# PennyMan_Ard_R3_Shield_v9.net
KiCad netlist of a schematic drawn in EAGLE
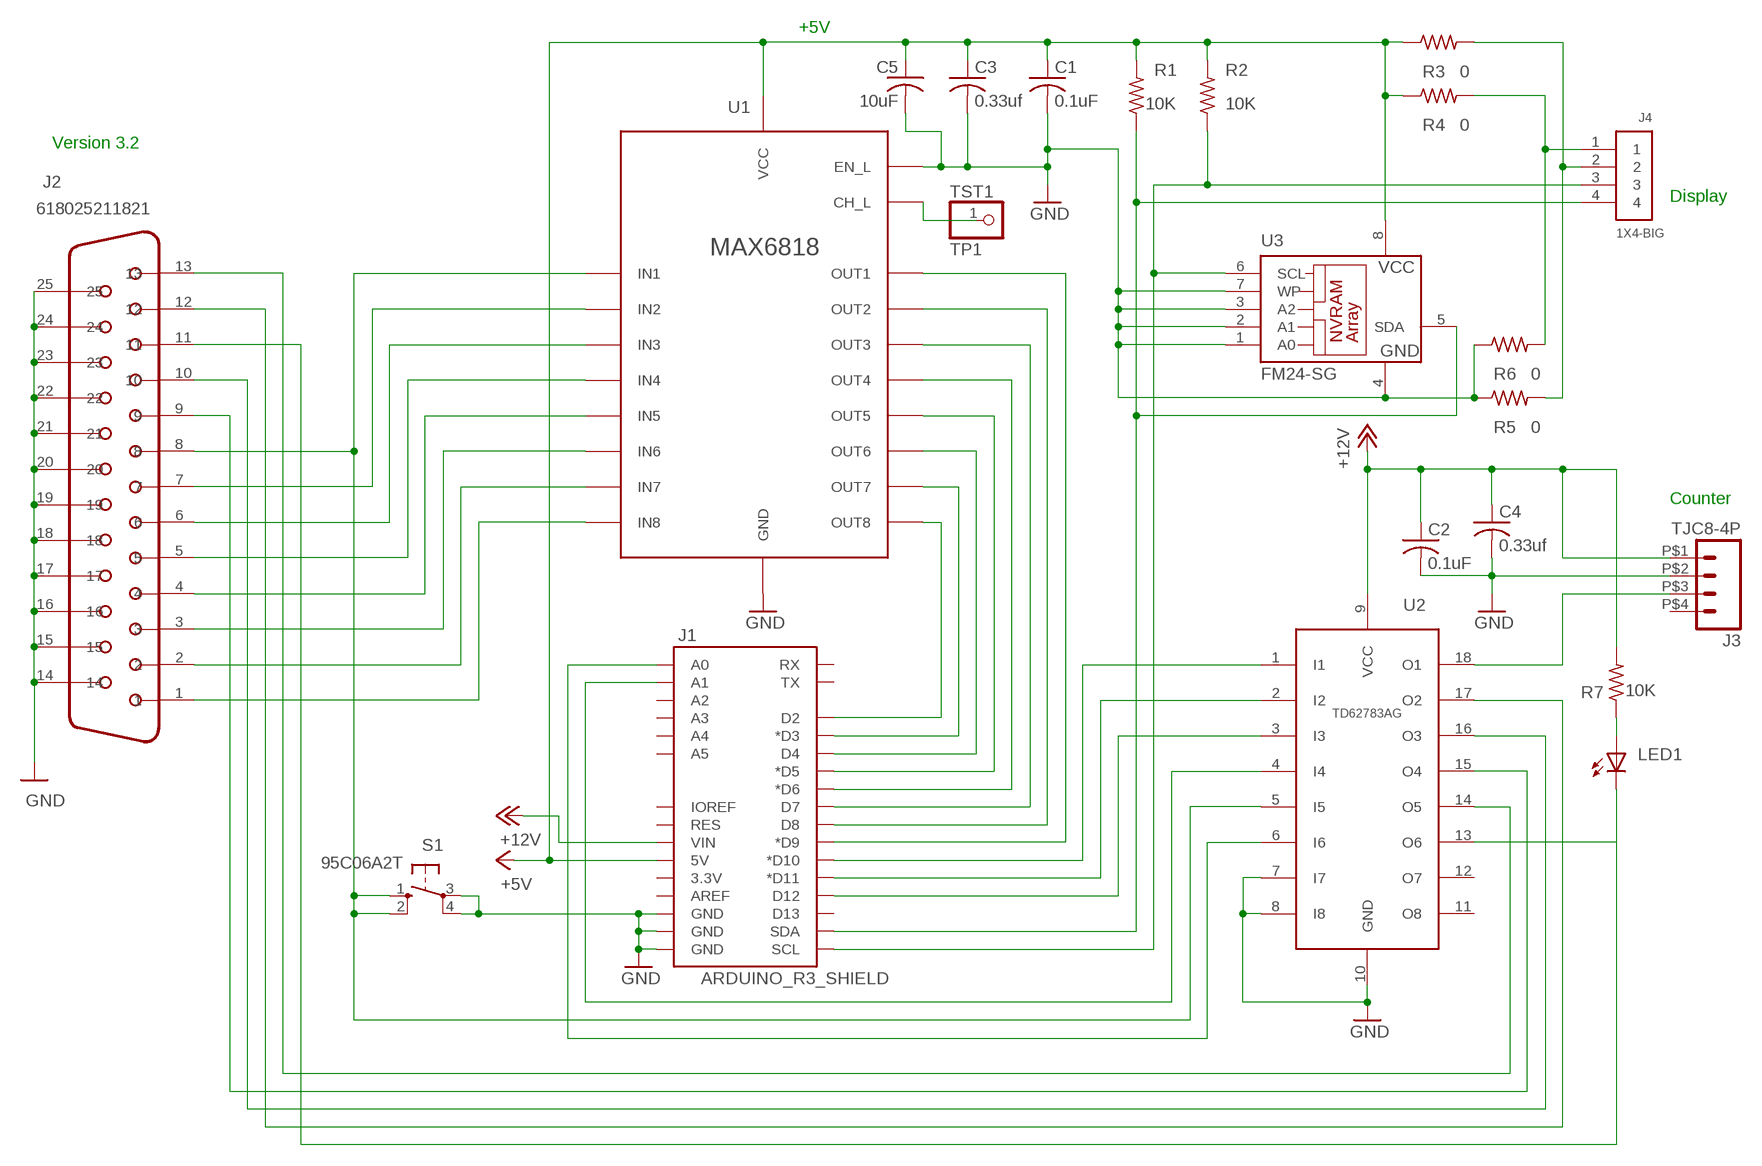
[diagram p0: schematic, sheet 1]

(export (version "E")
  (design (tool "Eeschema 10.0.6"))
  (components
    (comp (ref "C1")
      (value "0.1uF")
      (footprint "eagle-import:C0805")
      (libsource (lib "eagle-import") (part "C-USC0805"))
    )
    (comp (ref "C2")
      (value "0.1uF")
      (footprint "eagle-import:C0805")
      (libsource (lib "eagle-import") (part "C-USC0805"))
    )
    (comp (ref "C3")
      (value "0.33uf")
      (footprint "eagle-import:C1206")
      (libsource (lib "eagle-import") (part "C-USC1206"))
    )
    (comp (ref "C4")
      (value "0.33uf")
      (footprint "eagle-import:C1206")
      (libsource (lib "eagle-import") (part "C-USC1206"))
    )
    (comp (ref "C5")
      (value "10uF")
      (footprint "eagle-import:C1812")
      (libsource (lib "eagle-import") (part "C-USC1812"))
    )
    (comp (ref "J1")
      (value "ARDUINO_R3_SHIELD")
      (footprint "eagle-import:UNO_R3_SHIELD")
      (libsource (lib "eagle-import") (part "ARDUINO_R3_SHIELD"))
    )
    (comp (ref "J2")
      (value "618025211821")
      (footprint "eagle-import:618025211821")
      (libsource (lib "eagle-import") (part "618025211821"))
    )
    (comp (ref "J3")
      (value "TJC8-4P")
      (footprint "eagle-import:TJC8-4P")
      (libsource (lib "eagle-import") (part "TJC8-4P"))
    )
    (comp (ref "J4")
      (value "1X4-BIG")
      (footprint "eagle-import:1X04-BIG")
      (libsource (lib "eagle-import") (part "1X4-BIG"))
    )
    (comp (ref "LED1")
      (value "LEDSML0805")
      (footprint "eagle-import:SML0805")
      (libsource (lib "eagle-import") (part "LEDSML0805"))
    )
    (comp (ref "R1")
      (value "10K")
      (footprint "eagle-import:R0805")
      (libsource (lib "eagle-import") (part "R-US_R0805"))
    )
    (comp (ref "R2")
      (value "10K")
      (footprint "eagle-import:R0805")
      (libsource (lib "eagle-import") (part "R-US_R0805"))
    )
    (comp (ref "R3")
      (value "0")
      (footprint "eagle-import:R0805")
      (libsource (lib "eagle-import") (part "R-US_R0805"))
    )
    (comp (ref "R4")
      (value "0")
      (footprint "eagle-import:R0805")
      (libsource (lib "eagle-import") (part "R-US_R0805"))
    )
    (comp (ref "R5")
      (value "0")
      (footprint "eagle-import:R0805")
      (libsource (lib "eagle-import") (part "R-US_R0805"))
    )
    (comp (ref "R6")
      (value "0")
      (footprint "eagle-import:R0805")
      (libsource (lib "eagle-import") (part "R-US_R0805"))
    )
    (comp (ref "R7")
      (value "10K")
      (footprint "eagle-import:R0805")
      (libsource (lib "eagle-import") (part "R-US_R0805"))
    )
    (comp (ref "S1")
      (value "95C06A2T")
      (footprint "eagle-import:B3F-10XX")
      (libsource (lib "eagle-import") (part "10-XX"))
    )
    (comp (ref "TST1")
      (value "TP1")
      (footprint "eagle-import:1X01")
      (libsource (lib "eagle-import") (part "PINHD-1X1"))
    )
    (comp (ref "U1")
      (value "MAX6818")
      (footprint "eagle-import:SSOP20")
      (libsource (lib "eagle-import") (part "MAX6818"))
    )
    (comp (ref "U2")
      (value "TD62783AG")
      (footprint "eagle-import:SOP18")
      (libsource (lib "eagle-import") (part "TD62783AG"))
    )
    (comp (ref "U3")
      (value "FM24-SG")
      (footprint "eagle-import:SO8")
      (libsource (lib "eagle-import") (part "FM24-SG"))
    )
  )
  (nets
    (net (code "1") (name "+5V") (class "Default")
      (node (ref "C1") (pin "1") (pinfunction "1_1") (pintype "passive"))
      (node (ref "C3") (pin "1") (pinfunction "1_1") (pintype "passive"))
      (node (ref "C5") (pin "1") (pinfunction "1_1") (pintype "passive"))
      (node (ref "J1") (pin "5V") (pinfunction "5V_5V") (pintype "bidirectional"))
      (node (ref "R1") (pin "2") (pinfunction "2_2") (pintype "passive"))
      (node (ref "R2") (pin "2") (pinfunction "2_2") (pintype "passive"))
      (node (ref "R3") (pin "1") (pinfunction "1_1") (pintype "passive"))
      (node (ref "R4") (pin "1") (pinfunction "1_1") (pintype "passive"))
      (node (ref "U1") (pin "VCC") (pinfunction "VCC_VCC") (pintype "bidirectional"))
      (node (ref "U3") (pin "8") (pinfunction "VCC_8") (pintype "power_in"))
    )
    (net (code "2") (name "+12V") (class "Default")
      (node (ref "C2") (pin "1") (pinfunction "1_1") (pintype "passive"))
      (node (ref "C4") (pin "1") (pinfunction "1_1") (pintype "passive"))
      (node (ref "J1") (pin "VIN") (pinfunction "VIN_VIN") (pintype "bidirectional"))
      (node (ref "J3") (pin "P$1") (pinfunction "1_P$1") (pintype "passive"))
      (node (ref "R7") (pin "2") (pinfunction "2_2") (pintype "passive"))
      (node (ref "U2") (pin "9") (pinfunction "VCC_9") (pintype "bidirectional"))
    )
    (net (code "3") (name "GND") (class "Default")
      (node (ref "C1") (pin "2") (pinfunction "2_2") (pintype "passive"))
      (node (ref "C2") (pin "2") (pinfunction "2_2") (pintype "passive"))
      (node (ref "C3") (pin "2") (pinfunction "2_2") (pintype "passive"))
      (node (ref "C4") (pin "2") (pinfunction "2_2") (pintype "passive"))
      (node (ref "C5") (pin "2") (pinfunction "2_2") (pintype "passive"))
      (node (ref "J1") (pin "GND@0") (pinfunction "GND_GND@0") (pintype "bidirectional"))
      (node (ref "J1") (pin "GND@1") (pinfunction "GND_GND@1") (pintype "bidirectional"))
      (node (ref "J1") (pin "GND@2") (pinfunction "GND_GND@2") (pintype "bidirectional"))
      (node (ref "J2") (pin "14") (pinfunction "14_14") (pintype "bidirectional"))
      (node (ref "J2") (pin "15") (pinfunction "15_15") (pintype "bidirectional"))
      (node (ref "J2") (pin "16") (pinfunction "16_16") (pintype "bidirectional"))
      (node (ref "J2") (pin "17") (pinfunction "17_17") (pintype "bidirectional"))
      (node (ref "J2") (pin "18") (pinfunction "18_18") (pintype "bidirectional"))
      (node (ref "J2") (pin "19") (pinfunction "19_19") (pintype "bidirectional"))
      (node (ref "J2") (pin "20") (pinfunction "20_20") (pintype "bidirectional"))
      (node (ref "J2") (pin "21") (pinfunction "21_21") (pintype "bidirectional"))
      (node (ref "J2") (pin "22") (pinfunction "22_22") (pintype "bidirectional"))
      (node (ref "J2") (pin "23") (pinfunction "23_23") (pintype "bidirectional"))
      (node (ref "J2") (pin "24") (pinfunction "24_24") (pintype "bidirectional"))
      (node (ref "J2") (pin "25") (pinfunction "25_25") (pintype "bidirectional"))
      (node (ref "J3") (pin "P$2") (pinfunction "2_P$2") (pintype "passive"))
      (node (ref "R5") (pin "1") (pinfunction "1_1") (pintype "passive"))
      (node (ref "R6") (pin "1") (pinfunction "1_1") (pintype "passive"))
      (node (ref "S1") (pin "3") (pinfunction "P_3") (pintype "passive"))
      (node (ref "S1") (pin "4") (pinfunction "P1_4") (pintype "passive"))
      (node (ref "U1") (pin "EN_L") (pinfunction "EN_L_EN_L") (pintype "bidirectional"))
      (node (ref "U1") (pin "GND") (pinfunction "GND_GND") (pintype "bidirectional"))
      (node (ref "U2") (pin "10") (pinfunction "GND_10") (pintype "bidirectional"))
      (node (ref "U2") (pin "7") (pinfunction "I7_7") (pintype "bidirectional"))
      (node (ref "U2") (pin "8") (pinfunction "I8_8") (pintype "bidirectional"))
      (node (ref "U3") (pin "1") (pinfunction "A0_1") (pintype "passive"))
      (node (ref "U3") (pin "2") (pinfunction "A1_2") (pintype "passive"))
      (node (ref "U3") (pin "3") (pinfunction "A2_3") (pintype "passive"))
      (node (ref "U3") (pin "4") (pinfunction "GND_4") (pintype "power_in"))
      (node (ref "U3") (pin "7") (pinfunction "WP_7") (pintype "input"))
    )
    (net (code "4") (name "Net-(J1-*D3)") (class "Default")
      (node (ref "J1") (pin "D3") (pinfunction "*D3_D3") (pintype "bidirectional"))
      (node (ref "U1") (pin "OUT7") (pinfunction "OUT7_OUT7") (pintype "bidirectional"))
    )
    (net (code "5") (name "Net-(J1-*D5)") (class "Default")
      (node (ref "J1") (pin "D5") (pinfunction "*D5_D5") (pintype "bidirectional"))
      (node (ref "U1") (pin "OUT5") (pinfunction "OUT5_OUT5") (pintype "bidirectional"))
    )
    (net (code "6") (name "Net-(J1-*D6)") (class "Default")
      (node (ref "J1") (pin "D6") (pinfunction "*D6_D6") (pintype "bidirectional"))
      (node (ref "U1") (pin "OUT4") (pinfunction "OUT4_OUT4") (pintype "bidirectional"))
    )
    (net (code "7") (name "Net-(J1-*D9)") (class "Default")
      (node (ref "J1") (pin "D9") (pinfunction "*D9_D9") (pintype "bidirectional"))
      (node (ref "U1") (pin "OUT1") (pinfunction "OUT1_OUT1") (pintype "bidirectional"))
    )
    (net (code "8") (name "Net-(J1-*D10)") (class "Default")
      (node (ref "J1") (pin "D10") (pinfunction "*D10_D10") (pintype "bidirectional"))
      (node (ref "U2") (pin "1") (pinfunction "I1_1") (pintype "bidirectional"))
    )
    (net (code "9") (name "Net-(J1-*D11)") (class "Default")
      (node (ref "J1") (pin "D11") (pinfunction "*D11_D11") (pintype "bidirectional"))
      (node (ref "U2") (pin "2") (pinfunction "I2_2") (pintype "bidirectional"))
    )
    (net (code "10") (name "Net-(J1-PadD2)") (class "Default")
      (node (ref "J1") (pin "D2") (pinfunction "D2_D2") (pintype "bidirectional"))
      (node (ref "U1") (pin "OUT8") (pinfunction "OUT8_OUT8") (pintype "bidirectional"))
    )
    (net (code "11") (name "Net-(J1-PadD4)") (class "Default")
      (node (ref "J1") (pin "D4") (pinfunction "D4_D4") (pintype "bidirectional"))
      (node (ref "U1") (pin "OUT6") (pinfunction "OUT6_OUT6") (pintype "bidirectional"))
    )
    (net (code "12") (name "Net-(J1-PadD7)") (class "Default")
      (node (ref "J1") (pin "D7") (pinfunction "D7_D7") (pintype "bidirectional"))
      (node (ref "U1") (pin "OUT3") (pinfunction "OUT3_OUT3") (pintype "bidirectional"))
    )
    (net (code "13") (name "Net-(J1-PadD8)") (class "Default")
      (node (ref "J1") (pin "D8") (pinfunction "D8_D8") (pintype "bidirectional"))
      (node (ref "U1") (pin "OUT2") (pinfunction "OUT2_OUT2") (pintype "bidirectional"))
    )
    (net (code "14") (name "Net-(J2-Pad1)") (class "Default")
      (node (ref "J2") (pin "1") (pinfunction "1_1") (pintype "bidirectional"))
      (node (ref "U1") (pin "IN8") (pinfunction "IN8_IN8") (pintype "bidirectional"))
    )
    (net (code "15") (name "Net-(J2-Pad2)") (class "Default")
      (node (ref "J2") (pin "2") (pinfunction "2_2") (pintype "bidirectional"))
      (node (ref "U1") (pin "IN7") (pinfunction "IN7_IN7") (pintype "bidirectional"))
    )
    (net (code "16") (name "Net-(J2-Pad3)") (class "Default")
      (node (ref "J2") (pin "3") (pinfunction "3_3") (pintype "bidirectional"))
      (node (ref "U1") (pin "IN6") (pinfunction "IN6_IN6") (pintype "bidirectional"))
    )
    (net (code "17") (name "Net-(J2-Pad4)") (class "Default")
      (node (ref "J2") (pin "4") (pinfunction "4_4") (pintype "bidirectional"))
      (node (ref "U1") (pin "IN5") (pinfunction "IN5_IN5") (pintype "bidirectional"))
    )
    (net (code "18") (name "Net-(J2-Pad5)") (class "Default")
      (node (ref "J2") (pin "5") (pinfunction "5_5") (pintype "bidirectional"))
      (node (ref "U1") (pin "IN4") (pinfunction "IN4_IN4") (pintype "bidirectional"))
    )
    (net (code "19") (name "Net-(J2-Pad6)") (class "Default")
      (node (ref "J2") (pin "6") (pinfunction "6_6") (pintype "bidirectional"))
      (node (ref "U1") (pin "IN3") (pinfunction "IN3_IN3") (pintype "bidirectional"))
    )
    (net (code "20") (name "Net-(J2-Pad7)") (class "Default")
      (node (ref "J2") (pin "7") (pinfunction "7_7") (pintype "bidirectional"))
      (node (ref "U1") (pin "IN2") (pinfunction "IN2_IN2") (pintype "bidirectional"))
    )
    (net (code "21") (name "Net-(J3-3)") (class "Default")
      (node (ref "J3") (pin "P$3") (pinfunction "3_P$3") (pintype "passive"))
      (node (ref "U2") (pin "18") (pinfunction "O1_18") (pintype "bidirectional"))
    )
    (net (code "22") (name "Net-(J4-Pad1)") (class "Default")
      (node (ref "J4") (pin "1") (pinfunction "1_1") (pintype "bidirectional"))
      (node (ref "R4") (pin "2") (pinfunction "2_2") (pintype "passive"))
      (node (ref "R6") (pin "2") (pinfunction "2_2") (pintype "passive"))
    )
    (net (code "23") (name "Net-(J4-Pad2)") (class "Default")
      (node (ref "J4") (pin "2") (pinfunction "2_2") (pintype "bidirectional"))
      (node (ref "R3") (pin "2") (pinfunction "2_2") (pintype "passive"))
      (node (ref "R5") (pin "2") (pinfunction "2_2") (pintype "passive"))
    )
    (net (code "24") (name "Net-(LED1-PadA)") (class "Default")
      (node (ref "LED1") (pin "A") (pinfunction "A_A") (pintype "passive"))
      (node (ref "R7") (pin "1") (pinfunction "1_1") (pintype "passive"))
    )
    (net (code "25") (name "Net-(S1-S)") (class "Default")
      (node (ref "J2") (pin "8") (pinfunction "8_8") (pintype "bidirectional"))
      (node (ref "S1") (pin "1") (pinfunction "S_1") (pintype "passive"))
      (node (ref "S1") (pin "2") (pinfunction "S1_2") (pintype "passive"))
      (node (ref "U1") (pin "IN1") (pinfunction "IN1_IN1") (pintype "bidirectional"))
      (node (ref "U2") (pin "5") (pinfunction "I5_5") (pintype "bidirectional"))
    )
    (net (code "26") (name "Net-(TST1-Pad1)") (class "Default")
      (node (ref "TST1") (pin "1") (pinfunction "1_1") (pintype "passive"))
      (node (ref "U1") (pin "CH_L") (pinfunction "CH_L_CH_L") (pintype "bidirectional"))
    )
    (net (code "27") (name "Net-(U2-I3)") (class "Default")
      (node (ref "J1") (pin "D12") (pinfunction "D12_D12") (pintype "bidirectional"))
      (node (ref "U2") (pin "3") (pinfunction "I3_3") (pintype "bidirectional"))
    )
    (net (code "28") (name "Net-(U2-I4)") (class "Default")
      (node (ref "J1") (pin "A1") (pinfunction "A1_A1") (pintype "bidirectional"))
      (node (ref "U2") (pin "4") (pinfunction "I4_4") (pintype "bidirectional"))
    )
    (net (code "29") (name "Net-(U2-I6)") (class "Default")
      (node (ref "J1") (pin "A0") (pinfunction "A0_A0") (pintype "bidirectional"))
      (node (ref "U2") (pin "6") (pinfunction "I6_6") (pintype "bidirectional"))
    )
    (net (code "30") (name "Net-(U2-O2)") (class "Default")
      (node (ref "J2") (pin "12") (pinfunction "12_12") (pintype "bidirectional"))
      (node (ref "U2") (pin "17") (pinfunction "O2_17") (pintype "bidirectional"))
    )
    (net (code "31") (name "Net-(U2-O3)") (class "Default")
      (node (ref "J2") (pin "10") (pinfunction "10_10") (pintype "bidirectional"))
      (node (ref "U2") (pin "16") (pinfunction "O3_16") (pintype "bidirectional"))
    )
    (net (code "32") (name "Net-(U2-O4)") (class "Default")
      (node (ref "J2") (pin "9") (pinfunction "9_9") (pintype "bidirectional"))
      (node (ref "U2") (pin "15") (pinfunction "O4_15") (pintype "bidirectional"))
    )
    (net (code "33") (name "Net-(U2-O5)") (class "Default")
      (node (ref "J2") (pin "13") (pinfunction "13_13") (pintype "bidirectional"))
      (node (ref "U2") (pin "14") (pinfunction "O5_14") (pintype "bidirectional"))
    )
    (net (code "34") (name "Net-(U2-O6)") (class "Default")
      (node (ref "J2") (pin "11") (pinfunction "11_11") (pintype "bidirectional"))
      (node (ref "LED1") (pin "C") (pinfunction "C_C") (pintype "passive"))
      (node (ref "U2") (pin "13") (pinfunction "O6_13") (pintype "bidirectional"))
    )
    (net (code "35") (name "Net-(U3-SCL)") (class "Default")
      (node (ref "J1") (pin "SCL") (pinfunction "SCL_SCL") (pintype "bidirectional"))
      (node (ref "J4") (pin "3") (pinfunction "3_3") (pintype "bidirectional"))
      (node (ref "R2") (pin "1") (pinfunction "1_1") (pintype "passive"))
      (node (ref "U3") (pin "6") (pinfunction "SCL_6") (pintype "input"))
    )
    (net (code "36") (name "Net-(U3-SDA)") (class "Default")
      (node (ref "J1") (pin "SDA") (pinfunction "SDA_SDA") (pintype "bidirectional"))
      (node (ref "J4") (pin "4") (pinfunction "4_4") (pintype "bidirectional"))
      (node (ref "R1") (pin "1") (pinfunction "1_1") (pintype "passive"))
      (node (ref "U3") (pin "5") (pinfunction "SDA_5") (pintype "bidirectional"))
    )
    (net (code "37") (name "unconnected-(J1-Pad3.3V)") (class "Default")
      (node (ref "J1") (pin "3.3V") (pinfunction "3.3V_3.3V") (pintype "bidirectional"))
    )
    (net (code "38") (name "unconnected-(J1-PadA2)") (class "Default")
      (node (ref "J1") (pin "A2") (pinfunction "A2_A2") (pintype "bidirectional"))
    )
    (net (code "39") (name "unconnected-(J1-PadA3)") (class "Default")
      (node (ref "J1") (pin "A3") (pinfunction "A3_A3") (pintype "bidirectional"))
    )
    (net (code "40") (name "unconnected-(J1-PadA4)") (class "Default")
      (node (ref "J1") (pin "A4") (pinfunction "A4_A4") (pintype "bidirectional"))
    )
    (net (code "41") (name "unconnected-(J1-PadA5)") (class "Default")
      (node (ref "J1") (pin "A5") (pinfunction "A5_A5") (pintype "bidirectional"))
    )
    (net (code "42") (name "unconnected-(J1-PadAREF)") (class "Default")
      (node (ref "J1") (pin "AREF") (pinfunction "AREF_AREF") (pintype "bidirectional"))
    )
    (net (code "43") (name "unconnected-(J1-PadD13)") (class "Default")
      (node (ref "J1") (pin "D13") (pinfunction "D13_D13") (pintype "bidirectional"))
    )
    (net (code "44") (name "unconnected-(J1-PadIOREF)") (class "Default")
      (node (ref "J1") (pin "IOREF") (pinfunction "IOREF_IOREF") (pintype "bidirectional"))
    )
    (net (code "45") (name "unconnected-(J1-PadRES)") (class "Default")
      (node (ref "J1") (pin "RES") (pinfunction "RES_RES") (pintype "bidirectional"))
    )
    (net (code "46") (name "unconnected-(J1-PadRX)") (class "Default")
      (node (ref "J1") (pin "RX") (pinfunction "RX_RX") (pintype "bidirectional"))
    )
    (net (code "47") (name "unconnected-(J1-PadTX)") (class "Default")
      (node (ref "J1") (pin "TX") (pinfunction "TX_TX") (pintype "bidirectional"))
    )
    (net (code "48") (name "unconnected-(J3-4-PadP$4)") (class "Default")
      (node (ref "J3") (pin "P$4") (pinfunction "4_P$4") (pintype "passive"))
    )
    (net (code "49") (name "unconnected-(U2-O7-Pad12)") (class "Default")
      (node (ref "U2") (pin "12") (pinfunction "O7_12") (pintype "bidirectional"))
    )
    (net (code "50") (name "unconnected-(U2-O8-Pad11)") (class "Default")
      (node (ref "U2") (pin "11") (pinfunction "O8_11") (pintype "bidirectional"))
    )
  )
)
